# chyba_gotowe_nowe.net
KiCad netlist of a schematic drawn in EAGLE
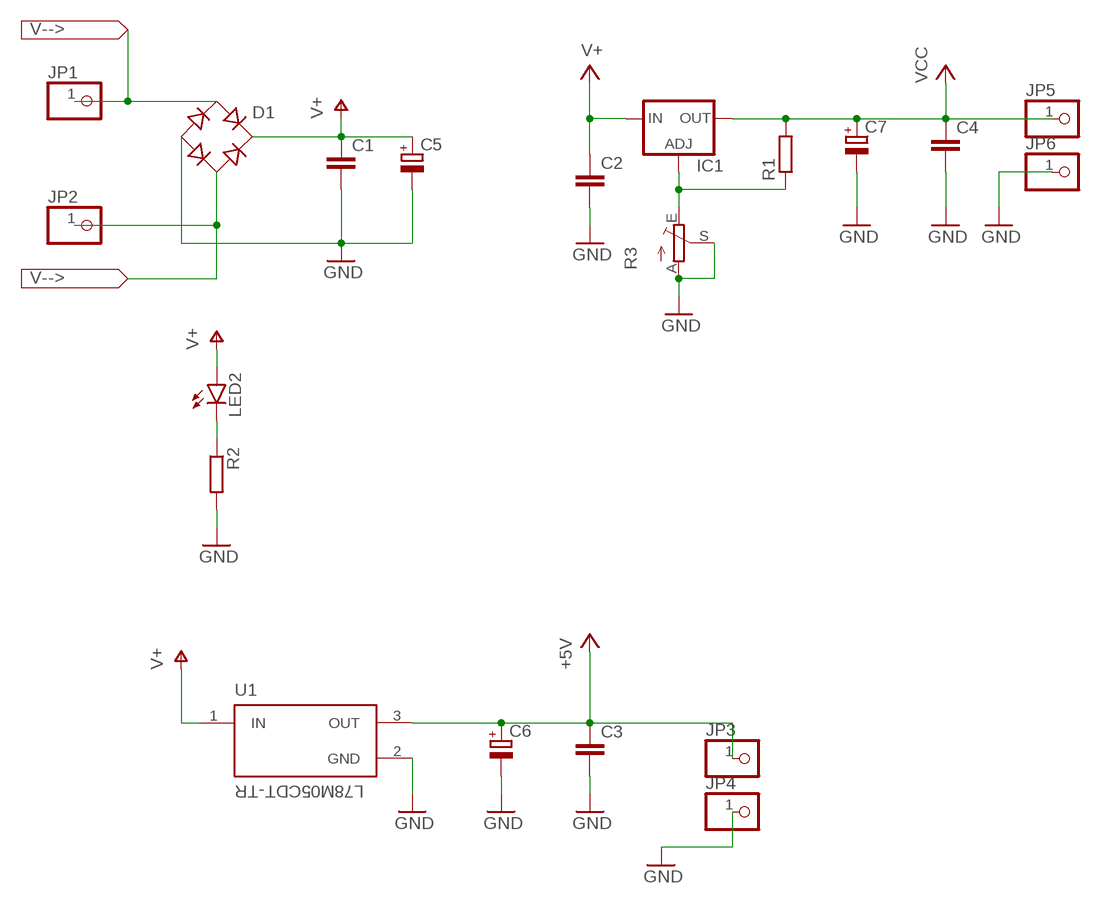
[diagram p0: schematic, sheet 1]

(export (version "E")
  (design (tool "Eeschema 10.0.6"))
  (components
    (comp (ref "C1")
      (value "C-EUC1206")
      (footprint "eagle-import:C1206")
      (libsource (lib "eagle-import") (part "C-EUC1206"))
    )
    (comp (ref "C2")
      (value "C-EUC1206")
      (footprint "eagle-import:C1206")
      (libsource (lib "eagle-import") (part "C-EUC1206"))
    )
    (comp (ref "C3")
      (value "C-EUC1206")
      (footprint "eagle-import:C1206")
      (libsource (lib "eagle-import") (part "C-EUC1206"))
    )
    (comp (ref "C4")
      (value "C-EUC1206")
      (footprint "eagle-import:C1206")
      (libsource (lib "eagle-import") (part "C-EUC1206"))
    )
    (comp (ref "C5")
      (value "CPOL-EUTT5D10")
      (footprint "eagle-import:TT5D10")
      (libsource (lib "eagle-import") (part "CPOL-EUTT5D10"))
    )
    (comp (ref "C6")
      (value "CPOL-EUTT5D10")
      (footprint "eagle-import:TT5D10")
      (libsource (lib "eagle-import") (part "CPOL-EUTT5D10"))
    )
    (comp (ref "C7")
      (value "CPOL-EUTT5D10")
      (footprint "eagle-import:TT5D10")
      (libsource (lib "eagle-import") (part "CPOL-EUTT5D10"))
    )
    (comp (ref "D1")
      (value "RECTIFIER-RB1A")
      (footprint "eagle-import:RB1A")
      (libsource (lib "eagle-import") (part "RECTIFIER-RB1A"))
    )
    (comp (ref "IC1")
      (value "LM317MSTT3")
      (footprint "eagle-import:SOT223")
      (libsource (lib "eagle-import") (part "LM317?MSTT3"))
    )
    (comp (ref "JP1")
      (value "PINHD-1X1")
      (footprint "eagle-import:1X01")
      (libsource (lib "eagle-import") (part "PINHD-1X1"))
    )
    (comp (ref "JP2")
      (value "PINHD-1X1")
      (footprint "eagle-import:1X01")
      (libsource (lib "eagle-import") (part "PINHD-1X1"))
    )
    (comp (ref "JP3")
      (value "PINHD-1X1")
      (footprint "eagle-import:1X01")
      (libsource (lib "eagle-import") (part "PINHD-1X1"))
    )
    (comp (ref "JP4")
      (value "PINHD-1X1")
      (footprint "eagle-import:1X01")
      (libsource (lib "eagle-import") (part "PINHD-1X1"))
    )
    (comp (ref "JP5")
      (value "PINHD-1X1")
      (footprint "eagle-import:1X01")
      (libsource (lib "eagle-import") (part "PINHD-1X1"))
    )
    (comp (ref "JP6")
      (value "PINHD-1X1")
      (footprint "eagle-import:1X01")
      (libsource (lib "eagle-import") (part "PINHD-1X1"))
    )
    (comp (ref "LED2")
      (value "LEDSMT1206")
      (footprint "eagle-import:1206")
      (libsource (lib "eagle-import") (part "LEDSMT1206"))
    )
    (comp (ref "R1")
      (value "R-EU_R1206")
      (footprint "eagle-import:R1206")
      (libsource (lib "eagle-import") (part "R-EU_R1206"))
    )
    (comp (ref "R2")
      (value "R-EU_R1206")
      (footprint "eagle-import:R1206")
      (libsource (lib "eagle-import") (part "R-EU_R1206"))
    )
    (comp (ref "R3")
      (value "TRIM_EU-PT10")
      (footprint "eagle-import:PT-10")
      (libsource (lib "eagle-import") (part "TRIM_EU-PT10"))
    )
    (comp (ref "U1")
      (value "L78M05CDT-TR")
      (footprint "eagle-import:VREG_L78M05CDT-TR")
      (fields (field (name "MANUFACTURER") "STMicroelectronics"))
      (libsource (lib "eagle-import") (part "L78M05CDT-TR"))
    )
  )
  (nets
    (net (code "1") (name "+5V") (class "Default")
      (node (ref "C3") (pin "1") (pinfunction "1_1") (pintype "passive"))
      (node (ref "C6") (pin "+") (pinfunction "+_+") (pintype "passive"))
      (node (ref "JP3") (pin "1") (pinfunction "1_1") (pintype "passive"))
      (node (ref "U1") (pin "3") (pinfunction "OUT_3") (pintype "output"))
    )
    (net (code "2") (name "GND") (class "Default")
      (node (ref "C1") (pin "2") (pinfunction "2_2") (pintype "passive"))
      (node (ref "C2") (pin "2") (pinfunction "2_2") (pintype "passive"))
      (node (ref "C3") (pin "2") (pinfunction "2_2") (pintype "passive"))
      (node (ref "C4") (pin "2") (pinfunction "2_2") (pintype "passive"))
      (node (ref "C5") (pin "-") (pinfunction "-_-") (pintype "passive"))
      (node (ref "C6") (pin "-") (pinfunction "-_-") (pintype "passive"))
      (node (ref "C7") (pin "-") (pinfunction "-_-") (pintype "passive"))
      (node (ref "D1") (pin "-") (pinfunction "-_-") (pintype "passive"))
      (node (ref "JP4") (pin "1") (pinfunction "1_1") (pintype "passive"))
      (node (ref "JP6") (pin "1") (pinfunction "1_1") (pintype "passive"))
      (node (ref "R2") (pin "2") (pinfunction "2_2") (pintype "passive"))
      (node (ref "R3") (pin "A") (pinfunction "A_A") (pintype "passive"))
      (node (ref "R3") (pin "S") (pinfunction "S_S") (pintype "passive"))
      (node (ref "U1") (pin "2") (pinfunction "GND_2") (pintype "power_in"))
    )
    (net (code "3") (name "Net-(D1-PadAC1)") (class "Default")
      (node (ref "D1") (pin "AC1") (pinfunction "AC1_AC1") (pintype "passive"))
      (node (ref "JP1") (pin "1") (pinfunction "1_1") (pintype "passive"))
    )
    (net (code "4") (name "Net-(D1-PadAC2)") (class "Default")
      (node (ref "D1") (pin "AC2") (pinfunction "AC2_AC2") (pintype "passive"))
      (node (ref "JP2") (pin "1") (pinfunction "1_1") (pintype "passive"))
    )
    (net (code "5") (name "Net-(IC1-ADJ)") (class "Default")
      (node (ref "IC1") (pin "1") (pinfunction "ADJ_1") (pintype "input"))
      (node (ref "R1") (pin "1") (pinfunction "1_1") (pintype "passive"))
      (node (ref "R3") (pin "E") (pinfunction "E_E") (pintype "passive"))
    )
    (net (code "6") (name "Net-(LED2-PadC)") (class "Default")
      (node (ref "LED2") (pin "C") (pinfunction "C_C") (pintype "passive"))
      (node (ref "R2") (pin "1") (pinfunction "1_1") (pintype "passive"))
    )
    (net (code "7") (name "V+") (class "Default")
      (node (ref "C1") (pin "1") (pinfunction "1_1") (pintype "passive"))
      (node (ref "C2") (pin "1") (pinfunction "1_1") (pintype "passive"))
      (node (ref "C5") (pin "+") (pinfunction "+_+") (pintype "passive"))
      (node (ref "D1") (pin "+") (pinfunction "+_+") (pintype "passive"))
      (node (ref "IC1") (pin "3") (pinfunction "IN_3") (pintype "input"))
      (node (ref "LED2") (pin "A") (pinfunction "A_A") (pintype "passive"))
      (node (ref "U1") (pin "1") (pinfunction "IN_1") (pintype "input"))
    )
    (net (code "8") (name "VCC") (class "Default")
      (node (ref "C4") (pin "1") (pinfunction "1_1") (pintype "passive"))
      (node (ref "C7") (pin "+") (pinfunction "+_+") (pintype "passive"))
      (node (ref "IC1") (pin "4") (pinfunction "OUT_4") (pintype "passive"))
      (node (ref "JP5") (pin "1") (pinfunction "1_1") (pintype "passive"))
      (node (ref "R1") (pin "2") (pinfunction "2_2") (pintype "passive"))
    )
  )
)
